# OPNpool_r4.net
KiCad netlist of a schematic drawn in EAGLE
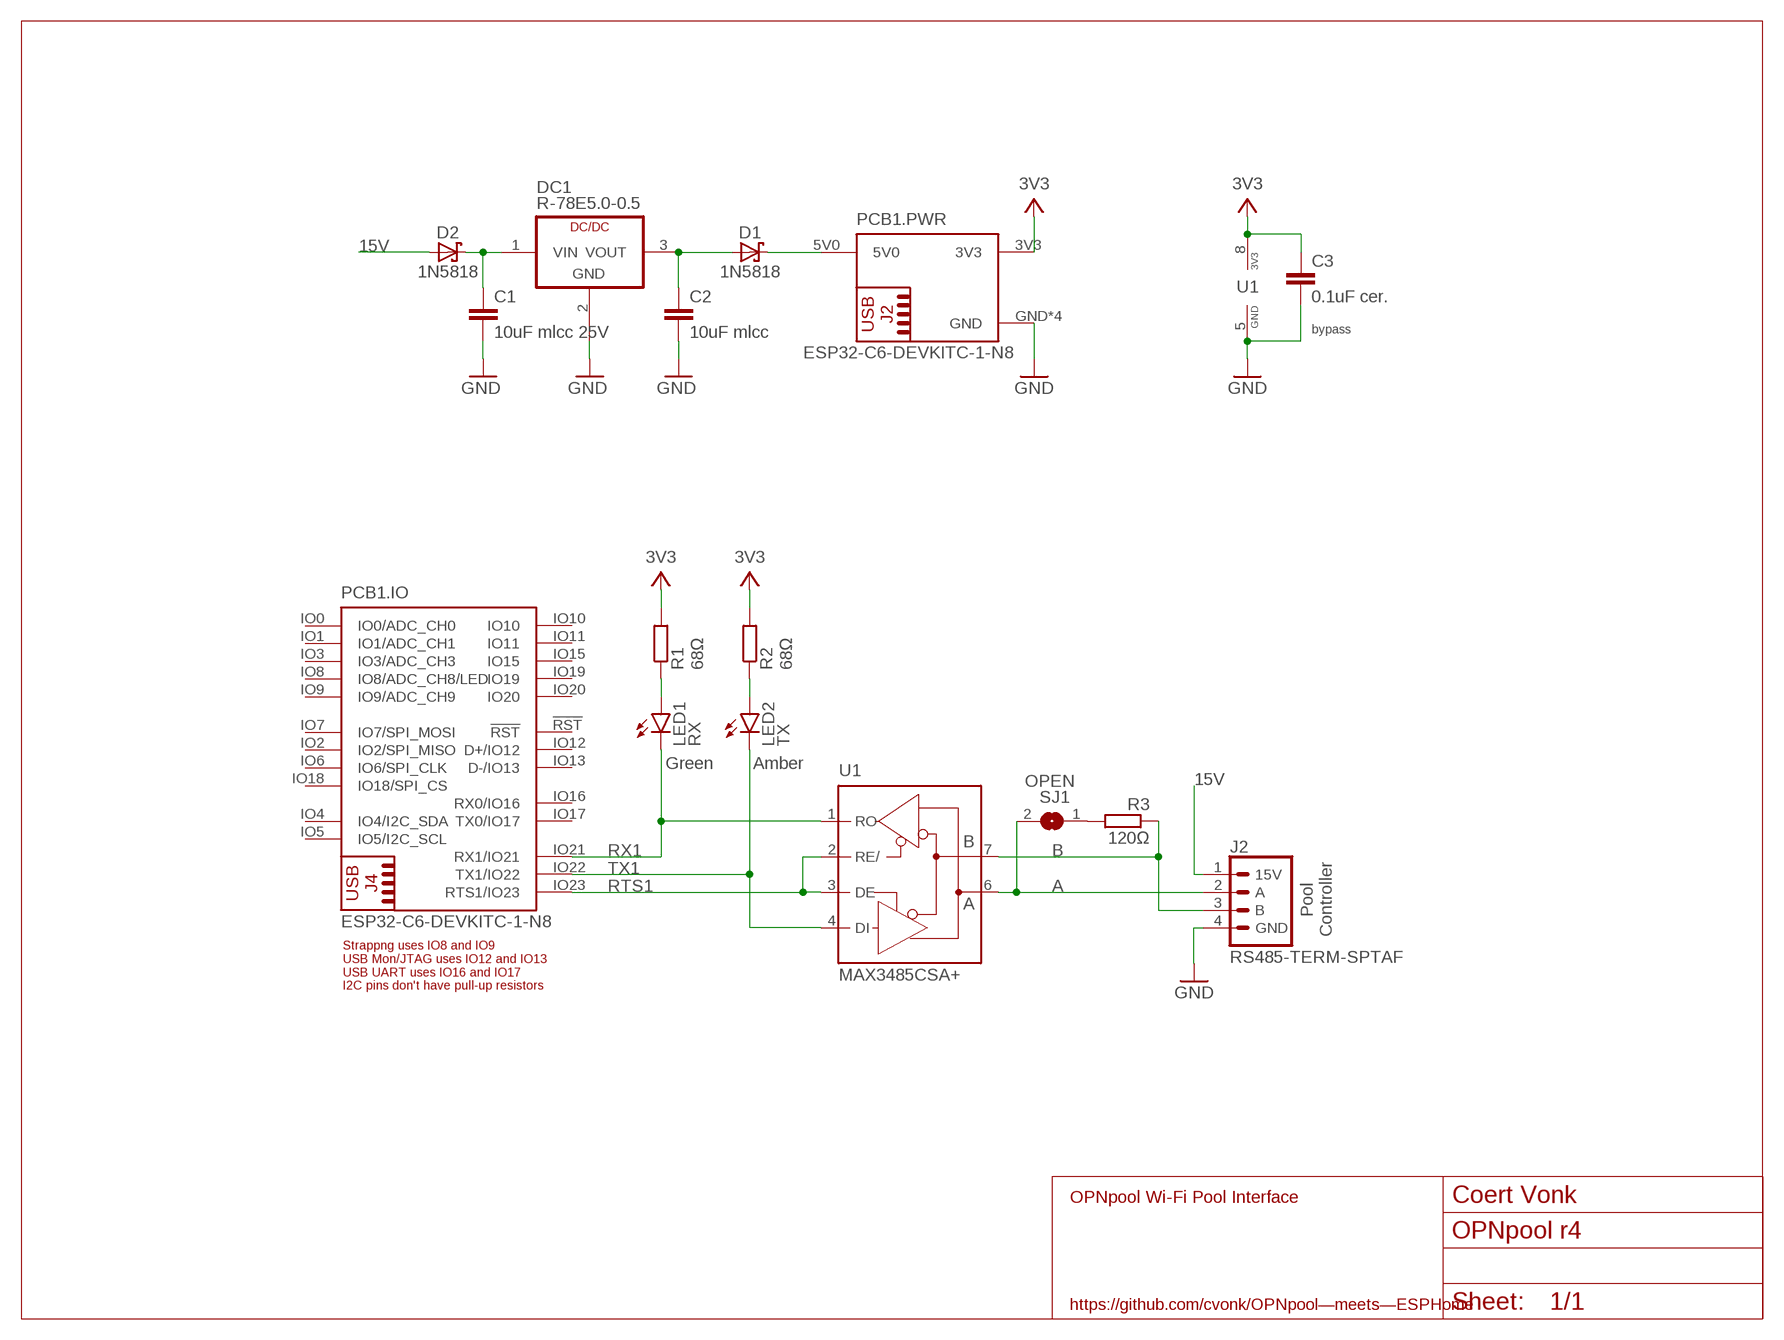
[diagram p0: schematic, sheet 1]

(export (version "E")
  (design (tool "Eeschema 10.0.6"))
  (components
    (comp (ref "C1")
      (value "10uF mlcc 25V")
      (footprint "eagle-import:C0805K")
      (fields (field (name "MANF") "Murata Electronics"))
      (libsource (lib "eagle-import") (part "C-EUC0805K"))
    )
    (comp (ref "C2")
      (value "10uF mlcc")
      (footprint "eagle-import:C0805K")
      (fields (field (name "MANF") "Murata Electronics"))
      (libsource (lib "eagle-import") (part "C-EUC0805K"))
    )
    (comp (ref "C3")
      (value "0.1uF cer.")
      (footprint "eagle-import:C0805K")
      (fields (field (name "MANF") "KEMET"))
      (libsource (lib "eagle-import") (part "C-EUC0805K"))
    )
    (comp (ref "D1")
      (value "1N5818")
      (footprint "eagle-import:DO41-7.6")
      (fields (field (name "MANF") "Rectron"))
      (libsource (lib "eagle-import") (part "1N5818"))
    )
    (comp (ref "D2")
      (value "1N5818")
      (footprint "eagle-import:DO41-7.6")
      (fields (field (name "MANF") "Rectron"))
      (libsource (lib "eagle-import") (part "1N5818"))
    )
    (comp (ref "DC1")
      (value "R-78E5.0-0.5")
      (footprint "eagle-import:SIP3")
      (fields (field (name "MANF") "RECOM Power"))
      (libsource (lib "eagle-import") (part "R-78E-0.55.0"))
    )
    (comp (ref "J2")
      (value "RS485-TERM-SPTAF")
      (footprint "eagle-import:SPTAF1_4-5,0-LL")
      (fields (field (name "MANF") "Phoenix Contact"))
      (libsource (lib "eagle-import") (part "RS485-TERM-SPTAF"))
    )
    (comp (ref "LED1")
      (value "RX")
      (footprint "eagle-import:CHIPLED_0805")
      (libsource (lib "eagle-import") (part "LEDCHIPLED_0805"))
    )
    (comp (ref "LED2")
      (value "TX")
      (footprint "eagle-import:CHIPLED_0805")
      (libsource (lib "eagle-import") (part "LEDCHIPLED_0805"))
    )
    (comp (ref "PCB1")
      (value "ESP32-C6-DEVKITC-1-N8")
      (footprint "eagle-import:MODULE_ESP32-C6-DEVKITC-1-N8")
      (libsource (lib "eagle-import") (part "ESP32-C6-DEVKITC-1-N8"))
    )
    (comp (ref "R1")
      (value "68Ω")
      (footprint "eagle-import:R0805")
      (fields (field (name "MANF") "Bourns"))
      (libsource (lib "eagle-import") (part "R-EU_R0805"))
    )
    (comp (ref "R2")
      (value "68Ω")
      (footprint "eagle-import:R0805")
      (fields (field (name "MANF") "Bourns"))
      (libsource (lib "eagle-import") (part "R-EU_R0805"))
    )
    (comp (ref "R3")
      (value "120Ω")
      (footprint "eagle-import:R0805")
      (fields (field (name "MANF") "Bourns"))
      (libsource (lib "eagle-import") (part "R-EU_R0805"))
    )
    (comp (ref "SJ1")
      (value "OPEN")
      (footprint "eagle-import:SJ")
      (libsource (lib "eagle-import") (part "SJ"))
    )
    (comp (ref "U1")
      (value "MAX3485CSA+")
      (footprint "eagle-import:SO08")
      (fields
        (field (name "MF") "MAXIM")
        (field (name "MPN") "MAX481CSA")
        (field (name "MANF") "Maxim Integrated")
        (field (name "MANF#") "MAX3485CSA+")
        (field (name "MOUSER#") "700-MAX3485CSA")
      )
      (libsource (lib "eagle-import") (part "MAX3485CSA+"))
    )
  )
  (nets
    (net (code "1") (name "/15V") (class "Default")
      (node (ref "D2") (pin "A") (pinfunction "A_A") (pintype "passive"))
      (node (ref "J2") (pin "1") (pinfunction "15V_1") (pintype "power_in"))
    )
    (net (code "2") (name "/A") (class "Default")
      (node (ref "J2") (pin "2") (pinfunction "A_2") (pintype "passive"))
      (node (ref "SJ1") (pin "2") (pinfunction "2_2") (pintype "passive"))
      (node (ref "U1") (pin "6") (pinfunction "A_6") (pintype "passive"))
    )
    (net (code "3") (name "/B") (class "Default")
      (node (ref "J2") (pin "3") (pinfunction "B_3") (pintype "passive"))
      (node (ref "R3") (pin "1") (pinfunction "1_1") (pintype "passive"))
      (node (ref "U1") (pin "7") (pinfunction "B_7") (pintype "passive"))
    )
    (net (code "4") (name "/RTS1") (class "Default")
      (node (ref "PCB1") (pin "IO23") (pinfunction "RTS1/IO23_IO23") (pintype "bidirectional"))
      (node (ref "U1") (pin "2") (pinfunction "RE/_2") (pintype "input"))
      (node (ref "U1") (pin "3") (pinfunction "DE_3") (pintype "input"))
    )
    (net (code "5") (name "/RX1") (class "Default")
      (node (ref "LED1") (pin "C") (pinfunction "C_C") (pintype "passive"))
      (node (ref "PCB1") (pin "IO21") (pinfunction "RX1/IO21_IO21") (pintype "bidirectional"))
      (node (ref "U1") (pin "1") (pinfunction "RO_1") (pintype "output"))
    )
    (net (code "6") (name "/TX1") (class "Default")
      (node (ref "LED2") (pin "C") (pinfunction "C_C") (pintype "passive"))
      (node (ref "PCB1") (pin "IO22") (pinfunction "TX1/IO22_IO22") (pintype "bidirectional"))
      (node (ref "U1") (pin "4") (pinfunction "DI_4") (pintype "input"))
    )
    (net (code "7") (name "3V3") (class "Default")
      (node (ref "C3") (pin "1") (pinfunction "1_1") (pintype "passive"))
      (node (ref "PCB1") (pin "3V3") (pinfunction "3V3_3V3") (pintype "power_in"))
      (node (ref "R1") (pin "2") (pinfunction "2_2") (pintype "passive"))
      (node (ref "R2") (pin "2") (pinfunction "2_2") (pintype "passive"))
      (node (ref "U1") (pin "8") (pinfunction "VCC_8") (pintype "passive"))
    )
    (net (code "8") (name "GND") (class "Default")
      (node (ref "C1") (pin "2") (pinfunction "2_2") (pintype "passive"))
      (node (ref "C2") (pin "2") (pinfunction "2_2") (pintype "passive"))
      (node (ref "C3") (pin "2") (pinfunction "2_2") (pintype "passive"))
      (node (ref "DC1") (pin "2") (pinfunction "GND_2") (pintype "power_in"))
      (node (ref "J2") (pin "4") (pinfunction "GND_4") (pintype "power_in"))
      (node (ref "PCB1") (pin "GND") (pinfunction "GND_GND") (pintype "power_in"))
      (node (ref "PCB1") (pin "GND@1") (pinfunction "GND_GND@1") (pintype "power_in"))
      (node (ref "PCB1") (pin "GND@2") (pinfunction "GND_GND@2") (pintype "power_in"))
      (node (ref "PCB1") (pin "GND@3") (pinfunction "GND_GND@3") (pintype "power_in"))
      (node (ref "U1") (pin "5") (pinfunction "GND_5") (pintype "power_in"))
    )
    (net (code "9") (name "Net-(D1-PadC)") (class "Default")
      (node (ref "D1") (pin "C") (pinfunction "C_C") (pintype "passive"))
      (node (ref "PCB1") (pin "5V0") (pinfunction "5V0_5V0") (pintype "power_in"))
    )
    (net (code "10") (name "Net-(DC1-VIN)") (class "Default")
      (node (ref "C1") (pin "1") (pinfunction "1_1") (pintype "passive"))
      (node (ref "D2") (pin "C") (pinfunction "C_C") (pintype "passive"))
      (node (ref "DC1") (pin "1") (pinfunction "VIN_1") (pintype "power_in"))
    )
    (net (code "11") (name "Net-(DC1-VOUT)") (class "Default")
      (node (ref "C2") (pin "1") (pinfunction "1_1") (pintype "passive"))
      (node (ref "D1") (pin "A") (pinfunction "A_A") (pintype "passive"))
      (node (ref "DC1") (pin "3") (pinfunction "VOUT_3") (pintype "power_in"))
    )
    (net (code "12") (name "Net-(LED1-PadA)") (class "Default")
      (node (ref "LED1") (pin "A") (pinfunction "A_A") (pintype "passive"))
      (node (ref "R1") (pin "1") (pinfunction "1_1") (pintype "passive"))
    )
    (net (code "13") (name "Net-(LED2-PadA)") (class "Default")
      (node (ref "LED2") (pin "A") (pinfunction "A_A") (pintype "passive"))
      (node (ref "R2") (pin "1") (pinfunction "1_1") (pintype "passive"))
    )
    (net (code "14") (name "Net-(R3-Pad2)") (class "Default")
      (node (ref "R3") (pin "2") (pinfunction "2_2") (pintype "passive"))
      (node (ref "SJ1") (pin "1") (pinfunction "1_1") (pintype "passive"))
    )
    (net (code "15") (name "unconnected-(PCB1-PadIO10)") (class "Default")
      (node (ref "PCB1") (pin "IO10") (pinfunction "IO10_IO10") (pintype "bidirectional"))
    )
    (net (code "16") (name "unconnected-(PCB1-PadIO11)") (class "Default")
      (node (ref "PCB1") (pin "IO11") (pinfunction "IO11_IO11") (pintype "bidirectional"))
    )
    (net (code "17") (name "unconnected-(PCB1-PadIO15)") (class "Default")
      (node (ref "PCB1") (pin "IO15") (pinfunction "IO15_IO15") (pintype "bidirectional"))
    )
    (net (code "18") (name "unconnected-(PCB1-PadIO19)") (class "Default")
      (node (ref "PCB1") (pin "IO19") (pinfunction "IO19_IO19") (pintype "bidirectional"))
    )
    (net (code "19") (name "unconnected-(PCB1-PadIO20)") (class "Default")
      (node (ref "PCB1") (pin "IO20") (pinfunction "IO20_IO20") (pintype "input"))
    )
    (net (code "20") (name "unconnected-(PCB1A-D+{slash}IO12-PadIO12)") (class "Default")
      (node (ref "PCB1") (pin "IO12") (pinfunction "D+/IO12_IO12") (pintype "input"))
    )
    (net (code "21") (name "unconnected-(PCB1A-D-{slash}IO13-PadIO13)") (class "Default")
      (node (ref "PCB1") (pin "IO13") (pinfunction "D-/IO13_IO13") (pintype "input"))
    )
    (net (code "22") (name "unconnected-(PCB1A-IO0{slash}ADC_CH0-PadIO0)") (class "Default")
      (node (ref "PCB1") (pin "IO0") (pinfunction "IO0/ADC_CH0_IO0") (pintype "bidirectional"))
    )
    (net (code "23") (name "unconnected-(PCB1A-IO1{slash}ADC_CH1-PadIO1)") (class "Default")
      (node (ref "PCB1") (pin "IO1") (pinfunction "IO1/ADC_CH1_IO1") (pintype "bidirectional"))
    )
    (net (code "24") (name "unconnected-(PCB1A-IO2{slash}SPI_MISO-PadIO2)") (class "Default")
      (node (ref "PCB1") (pin "IO2") (pinfunction "IO2/SPI_MISO_IO2") (pintype "bidirectional"))
    )
    (net (code "25") (name "unconnected-(PCB1A-IO3{slash}ADC_CH3-PadIO3)") (class "Default")
      (node (ref "PCB1") (pin "IO3") (pinfunction "IO3/ADC_CH3_IO3") (pintype "bidirectional"))
    )
    (net (code "26") (name "unconnected-(PCB1A-IO4{slash}I2C_SDA-PadIO4)") (class "Default")
      (node (ref "PCB1") (pin "IO4") (pinfunction "IO4/I2C_SDA_IO4") (pintype "bidirectional"))
    )
    (net (code "27") (name "unconnected-(PCB1A-IO5{slash}I2C_SCL-PadIO5)") (class "Default")
      (node (ref "PCB1") (pin "IO5") (pinfunction "IO5/I2C_SCL_IO5") (pintype "bidirectional"))
    )
    (net (code "28") (name "unconnected-(PCB1A-IO6{slash}SPI_CLK-PadIO6)") (class "Default")
      (node (ref "PCB1") (pin "IO6") (pinfunction "IO6/SPI_CLK_IO6") (pintype "bidirectional"))
    )
    (net (code "29") (name "unconnected-(PCB1A-IO7{slash}SPI_MOSI-PadIO7)") (class "Default")
      (node (ref "PCB1") (pin "IO7") (pinfunction "IO7/SPI_MOSI_IO7") (pintype "bidirectional"))
    )
    (net (code "30") (name "unconnected-(PCB1A-IO8{slash}ADC_CH8{slash}LED-PadIO8)") (class "Default")
      (node (ref "PCB1") (pin "IO8") (pinfunction "IO8/ADC_CH8/LED_IO8") (pintype "bidirectional"))
    )
    (net (code "31") (name "unconnected-(PCB1A-IO9{slash}ADC_CH9-PadIO9)") (class "Default")
      (node (ref "PCB1") (pin "IO9") (pinfunction "IO9/ADC_CH9_IO9") (pintype "bidirectional"))
    )
    (net (code "32") (name "unconnected-(PCB1A-IO18{slash}SPI_CS-PadIO18)") (class "Default")
      (node (ref "PCB1") (pin "IO18") (pinfunction "IO18/SPI_CS_IO18") (pintype "bidirectional"))
    )
    (net (code "33") (name "unconnected-(PCB1A-RX0{slash}IO16-PadIO16)") (class "Default")
      (node (ref "PCB1") (pin "IO16") (pinfunction "RX0/IO16_IO16") (pintype "bidirectional"))
    )
    (net (code "34") (name "unconnected-(PCB1A-TX0{slash}IO17-PadIO17)") (class "Default")
      (node (ref "PCB1") (pin "IO17") (pinfunction "TX0/IO17_IO17") (pintype "bidirectional"))
    )
    (net (code "35") (name "unconnected-(PCB1A-~{RST}-Pad!RST)") (class "Default")
      (node (ref "PCB1") (pin "!RST") (pinfunction "~{RST}_!RST") (pintype "input"))
    )
  )
)
